# 3-to-8_Decoder.net
KiCad netlist of a schematic drawn in EAGLE
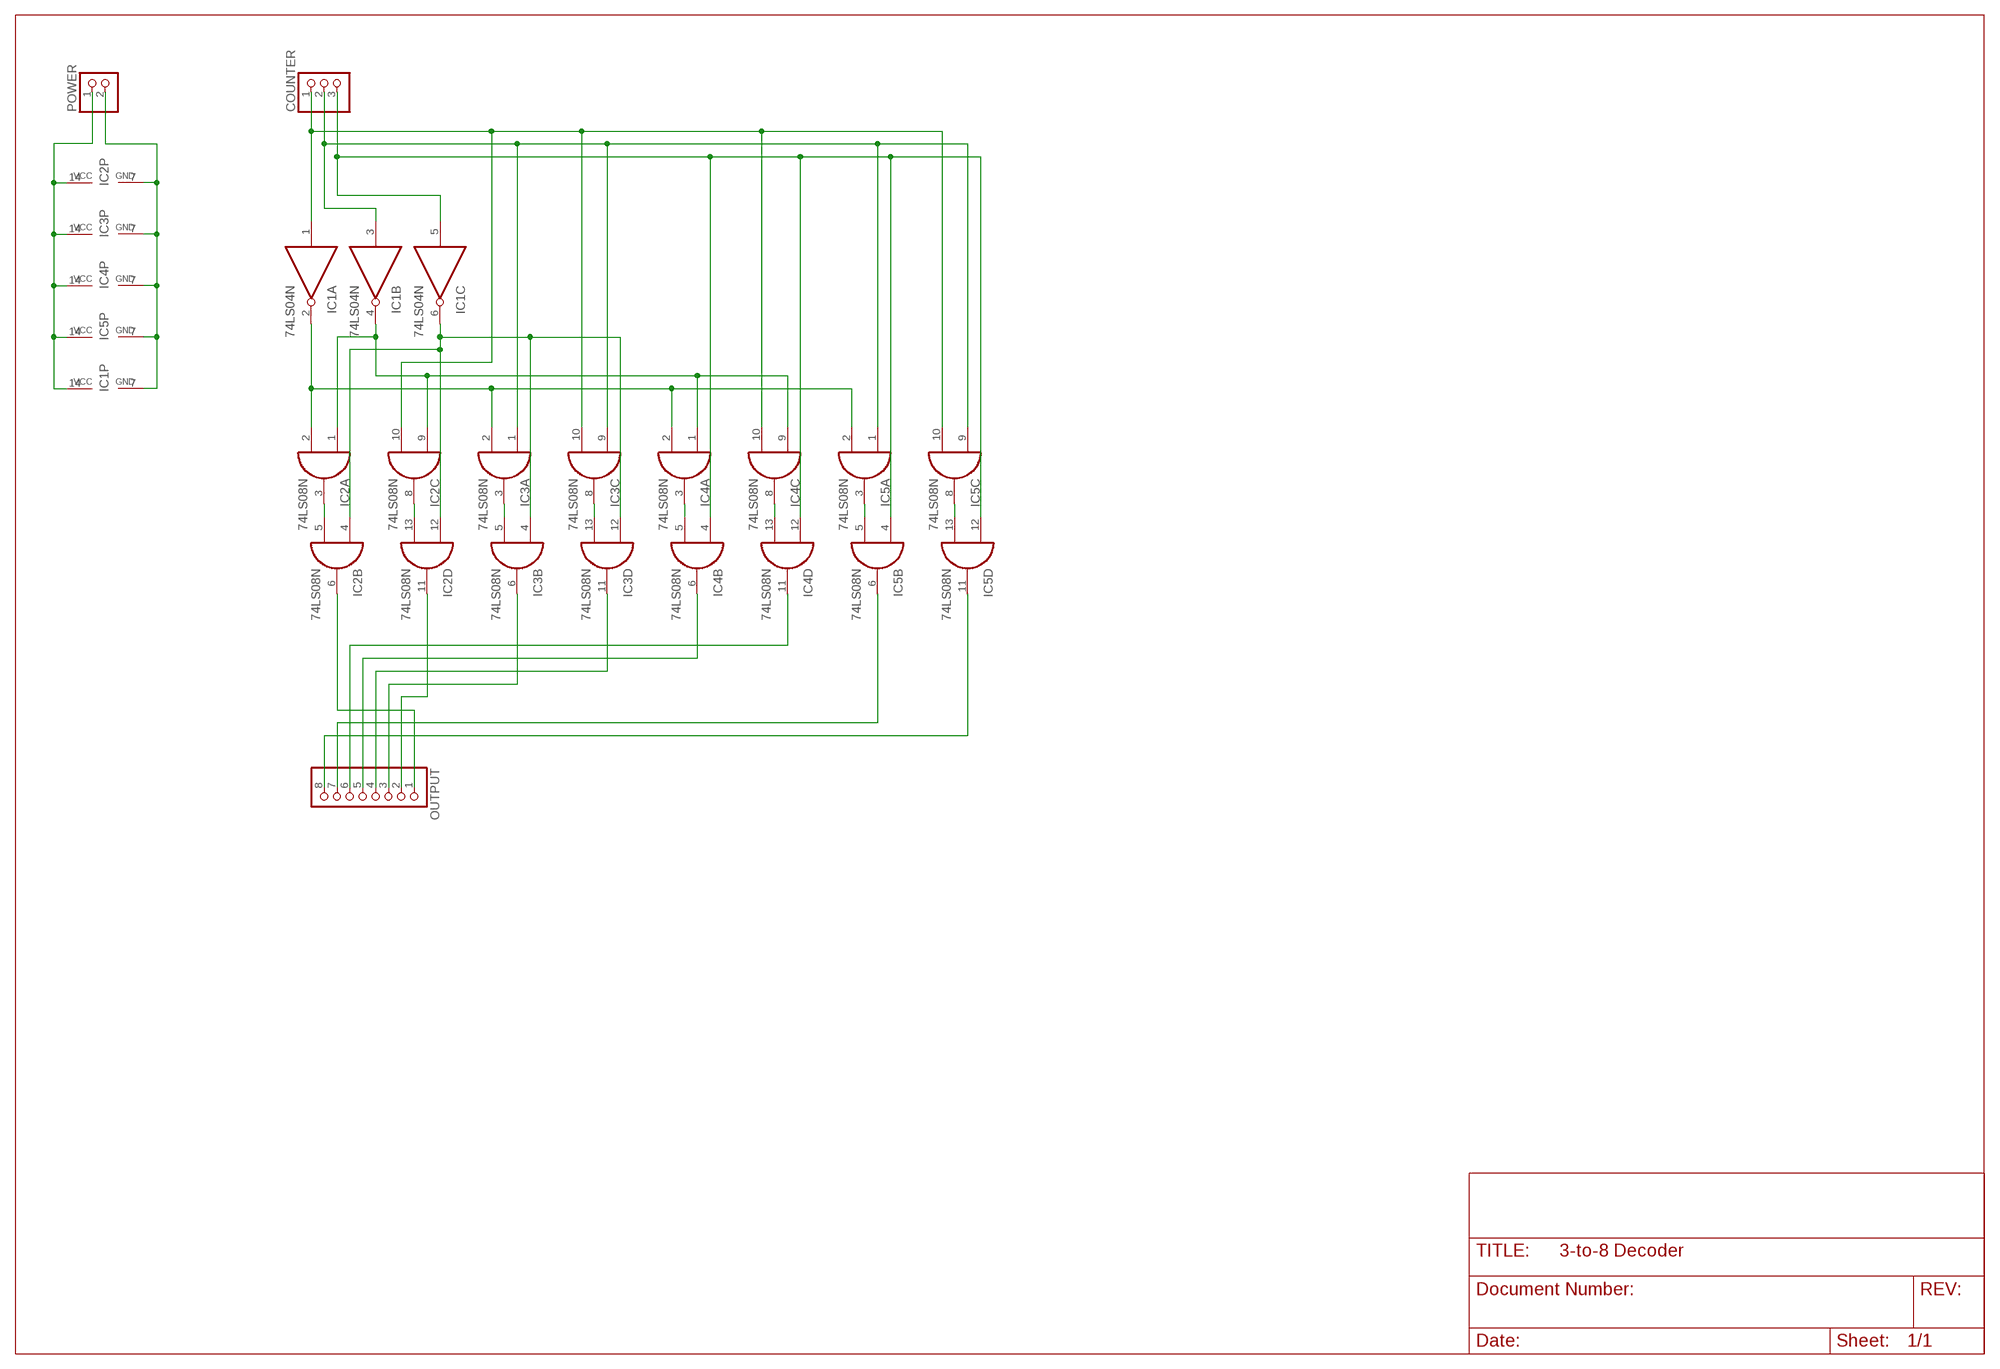
[diagram p0: schematic, sheet 1]

(export (version "E")
  (design (tool "Eeschema 10.0.6"))
  (components
    (comp (ref "COUNTER")
      (value "PINHD-1X3")
      (footprint "eagle-import:1X03")
      (libsource (lib "eagle-import") (part "PINHD-1X3"))
    )
    (comp (ref "IC1")
      (value "74LS04N")
      (footprint "eagle-import:DIL14")
      (libsource (lib "eagle-import") (part "7404NLS"))
    )
    (comp (ref "IC2")
      (value "74LS08N")
      (footprint "eagle-import:DIL14")
      (libsource (lib "eagle-import") (part "7408NLS"))
    )
    (comp (ref "IC3")
      (value "74LS08N")
      (footprint "eagle-import:DIL14")
      (libsource (lib "eagle-import") (part "7408NLS"))
    )
    (comp (ref "IC4")
      (value "74LS08N")
      (footprint "eagle-import:DIL14")
      (libsource (lib "eagle-import") (part "7408NLS"))
    )
    (comp (ref "IC5")
      (value "74LS08N")
      (footprint "eagle-import:DIL14")
      (libsource (lib "eagle-import") (part "7408NLS"))
    )
    (comp (ref "OUTPUT")
      (value "PINHD-1X8")
      (footprint "eagle-import:1X08")
      (libsource (lib "eagle-import") (part "PINHD-1X8"))
    )
    (comp (ref "POWER")
      (value "PINHD-1X2")
      (footprint "eagle-import:1X02")
      (libsource (lib "eagle-import") (part "PINHD-1X2"))
    )
  )
  (nets
    (net (code "1") (name "Net-(IC1A-I)") (class "Default")
      (node (ref "COUNTER") (pin "1") (pinfunction "1_1") (pintype "passive"))
      (node (ref "IC1") (pin "1") (pinfunction "I_1") (pintype "input"))
      (node (ref "IC2") (pin "10") (pinfunction "I1_10") (pintype "input"))
      (node (ref "IC3") (pin "10") (pinfunction "I1_10") (pintype "input"))
      (node (ref "IC4") (pin "10") (pinfunction "I1_10") (pintype "input"))
      (node (ref "IC5") (pin "10") (pinfunction "I1_10") (pintype "input"))
    )
    (net (code "2") (name "Net-(IC1A-O)") (class "Default")
      (node (ref "IC1") (pin "2") (pinfunction "O_2") (pintype "output"))
      (node (ref "IC2") (pin "2") (pinfunction "I1_2") (pintype "input"))
      (node (ref "IC3") (pin "2") (pinfunction "I1_2") (pintype "input"))
      (node (ref "IC4") (pin "2") (pinfunction "I1_2") (pintype "input"))
      (node (ref "IC5") (pin "2") (pinfunction "I1_2") (pintype "input"))
    )
    (net (code "3") (name "Net-(IC1B-I)") (class "Default")
      (node (ref "COUNTER") (pin "2") (pinfunction "2_2") (pintype "passive"))
      (node (ref "IC1") (pin "3") (pinfunction "I_3") (pintype "input"))
      (node (ref "IC3") (pin "1") (pinfunction "I0_1") (pintype "input"))
      (node (ref "IC3") (pin "9") (pinfunction "I0_9") (pintype "input"))
      (node (ref "IC5") (pin "1") (pinfunction "I0_1") (pintype "input"))
      (node (ref "IC5") (pin "9") (pinfunction "I0_9") (pintype "input"))
    )
    (net (code "4") (name "Net-(IC1B-O)") (class "Default")
      (node (ref "IC1") (pin "4") (pinfunction "O_4") (pintype "output"))
      (node (ref "IC2") (pin "1") (pinfunction "I0_1") (pintype "input"))
      (node (ref "IC2") (pin "9") (pinfunction "I0_9") (pintype "input"))
      (node (ref "IC4") (pin "1") (pinfunction "I0_1") (pintype "input"))
      (node (ref "IC4") (pin "9") (pinfunction "I0_9") (pintype "input"))
    )
    (net (code "5") (name "Net-(IC1C-I)") (class "Default")
      (node (ref "COUNTER") (pin "3") (pinfunction "3_3") (pintype "passive"))
      (node (ref "IC1") (pin "5") (pinfunction "I_5") (pintype "input"))
      (node (ref "IC4") (pin "12") (pinfunction "I0_12") (pintype "input"))
      (node (ref "IC4") (pin "4") (pinfunction "I0_4") (pintype "input"))
      (node (ref "IC5") (pin "12") (pinfunction "I0_12") (pintype "input"))
      (node (ref "IC5") (pin "4") (pinfunction "I0_4") (pintype "input"))
    )
    (net (code "6") (name "Net-(IC1C-O)") (class "Default")
      (node (ref "IC1") (pin "6") (pinfunction "O_6") (pintype "output"))
      (node (ref "IC2") (pin "12") (pinfunction "I0_12") (pintype "input"))
      (node (ref "IC2") (pin "4") (pinfunction "I0_4") (pintype "input"))
      (node (ref "IC3") (pin "12") (pinfunction "I0_12") (pintype "input"))
      (node (ref "IC3") (pin "4") (pinfunction "I0_4") (pintype "input"))
    )
    (net (code "7") (name "Net-(IC1G-GND)") (class "Default")
      (node (ref "IC1") (pin "7") (pinfunction "GND_7") (pintype "power_in"))
      (node (ref "IC2") (pin "7") (pinfunction "GND_7") (pintype "power_in"))
      (node (ref "IC3") (pin "7") (pinfunction "GND_7") (pintype "power_in"))
      (node (ref "IC4") (pin "7") (pinfunction "GND_7") (pintype "power_in"))
      (node (ref "IC5") (pin "7") (pinfunction "GND_7") (pintype "power_in"))
      (node (ref "POWER") (pin "2") (pinfunction "2_2") (pintype "passive"))
    )
    (net (code "8") (name "Net-(IC1G-VCC)") (class "Default")
      (node (ref "IC1") (pin "14") (pinfunction "VCC_14") (pintype "power_in"))
      (node (ref "IC2") (pin "14") (pinfunction "VCC_14") (pintype "power_in"))
      (node (ref "IC3") (pin "14") (pinfunction "VCC_14") (pintype "power_in"))
      (node (ref "IC4") (pin "14") (pinfunction "VCC_14") (pintype "power_in"))
      (node (ref "IC5") (pin "14") (pinfunction "VCC_14") (pintype "power_in"))
      (node (ref "POWER") (pin "1") (pinfunction "1_1") (pintype "passive"))
    )
    (net (code "9") (name "Net-(IC2A-O)") (class "Default")
      (node (ref "IC2") (pin "3") (pinfunction "O_3") (pintype "output"))
      (node (ref "IC2") (pin "5") (pinfunction "I1_5") (pintype "input"))
    )
    (net (code "10") (name "Net-(IC2B-O)") (class "Default")
      (node (ref "IC2") (pin "6") (pinfunction "O_6") (pintype "output"))
      (node (ref "OUTPUT") (pin "1") (pinfunction "1_1") (pintype "passive"))
    )
    (net (code "11") (name "Net-(IC2C-O)") (class "Default")
      (node (ref "IC2") (pin "13") (pinfunction "I1_13") (pintype "input"))
      (node (ref "IC2") (pin "8") (pinfunction "O_8") (pintype "output"))
    )
    (net (code "12") (name "Net-(IC2D-O)") (class "Default")
      (node (ref "IC2") (pin "11") (pinfunction "O_11") (pintype "output"))
      (node (ref "OUTPUT") (pin "2") (pinfunction "2_2") (pintype "passive"))
    )
    (net (code "13") (name "Net-(IC3A-O)") (class "Default")
      (node (ref "IC3") (pin "3") (pinfunction "O_3") (pintype "output"))
      (node (ref "IC3") (pin "5") (pinfunction "I1_5") (pintype "input"))
    )
    (net (code "14") (name "Net-(IC3B-O)") (class "Default")
      (node (ref "IC3") (pin "6") (pinfunction "O_6") (pintype "output"))
      (node (ref "OUTPUT") (pin "3") (pinfunction "3_3") (pintype "passive"))
    )
    (net (code "15") (name "Net-(IC3C-O)") (class "Default")
      (node (ref "IC3") (pin "13") (pinfunction "I1_13") (pintype "input"))
      (node (ref "IC3") (pin "8") (pinfunction "O_8") (pintype "output"))
    )
    (net (code "16") (name "Net-(IC3D-O)") (class "Default")
      (node (ref "IC3") (pin "11") (pinfunction "O_11") (pintype "output"))
      (node (ref "OUTPUT") (pin "4") (pinfunction "4_4") (pintype "passive"))
    )
    (net (code "17") (name "Net-(IC4A-O)") (class "Default")
      (node (ref "IC4") (pin "3") (pinfunction "O_3") (pintype "output"))
      (node (ref "IC4") (pin "5") (pinfunction "I1_5") (pintype "input"))
    )
    (net (code "18") (name "Net-(IC4B-O)") (class "Default")
      (node (ref "IC4") (pin "6") (pinfunction "O_6") (pintype "output"))
      (node (ref "OUTPUT") (pin "5") (pinfunction "5_5") (pintype "passive"))
    )
    (net (code "19") (name "Net-(IC4C-O)") (class "Default")
      (node (ref "IC4") (pin "13") (pinfunction "I1_13") (pintype "input"))
      (node (ref "IC4") (pin "8") (pinfunction "O_8") (pintype "output"))
    )
    (net (code "20") (name "Net-(IC4D-O)") (class "Default")
      (node (ref "IC4") (pin "11") (pinfunction "O_11") (pintype "output"))
      (node (ref "OUTPUT") (pin "6") (pinfunction "6_6") (pintype "passive"))
    )
    (net (code "21") (name "Net-(IC5A-O)") (class "Default")
      (node (ref "IC5") (pin "3") (pinfunction "O_3") (pintype "output"))
      (node (ref "IC5") (pin "5") (pinfunction "I1_5") (pintype "input"))
    )
    (net (code "22") (name "Net-(IC5B-O)") (class "Default")
      (node (ref "IC5") (pin "6") (pinfunction "O_6") (pintype "output"))
      (node (ref "OUTPUT") (pin "7") (pinfunction "7_7") (pintype "passive"))
    )
    (net (code "23") (name "Net-(IC5C-O)") (class "Default")
      (node (ref "IC5") (pin "13") (pinfunction "I1_13") (pintype "input"))
      (node (ref "IC5") (pin "8") (pinfunction "O_8") (pintype "output"))
    )
    (net (code "24") (name "Net-(IC5D-O)") (class "Default")
      (node (ref "IC5") (pin "11") (pinfunction "O_11") (pintype "output"))
      (node (ref "OUTPUT") (pin "8") (pinfunction "8_8") (pintype "passive"))
    )
  )
)
